# Sheet4.net
KiCad netlist of a schematic drawn in Altium Designer
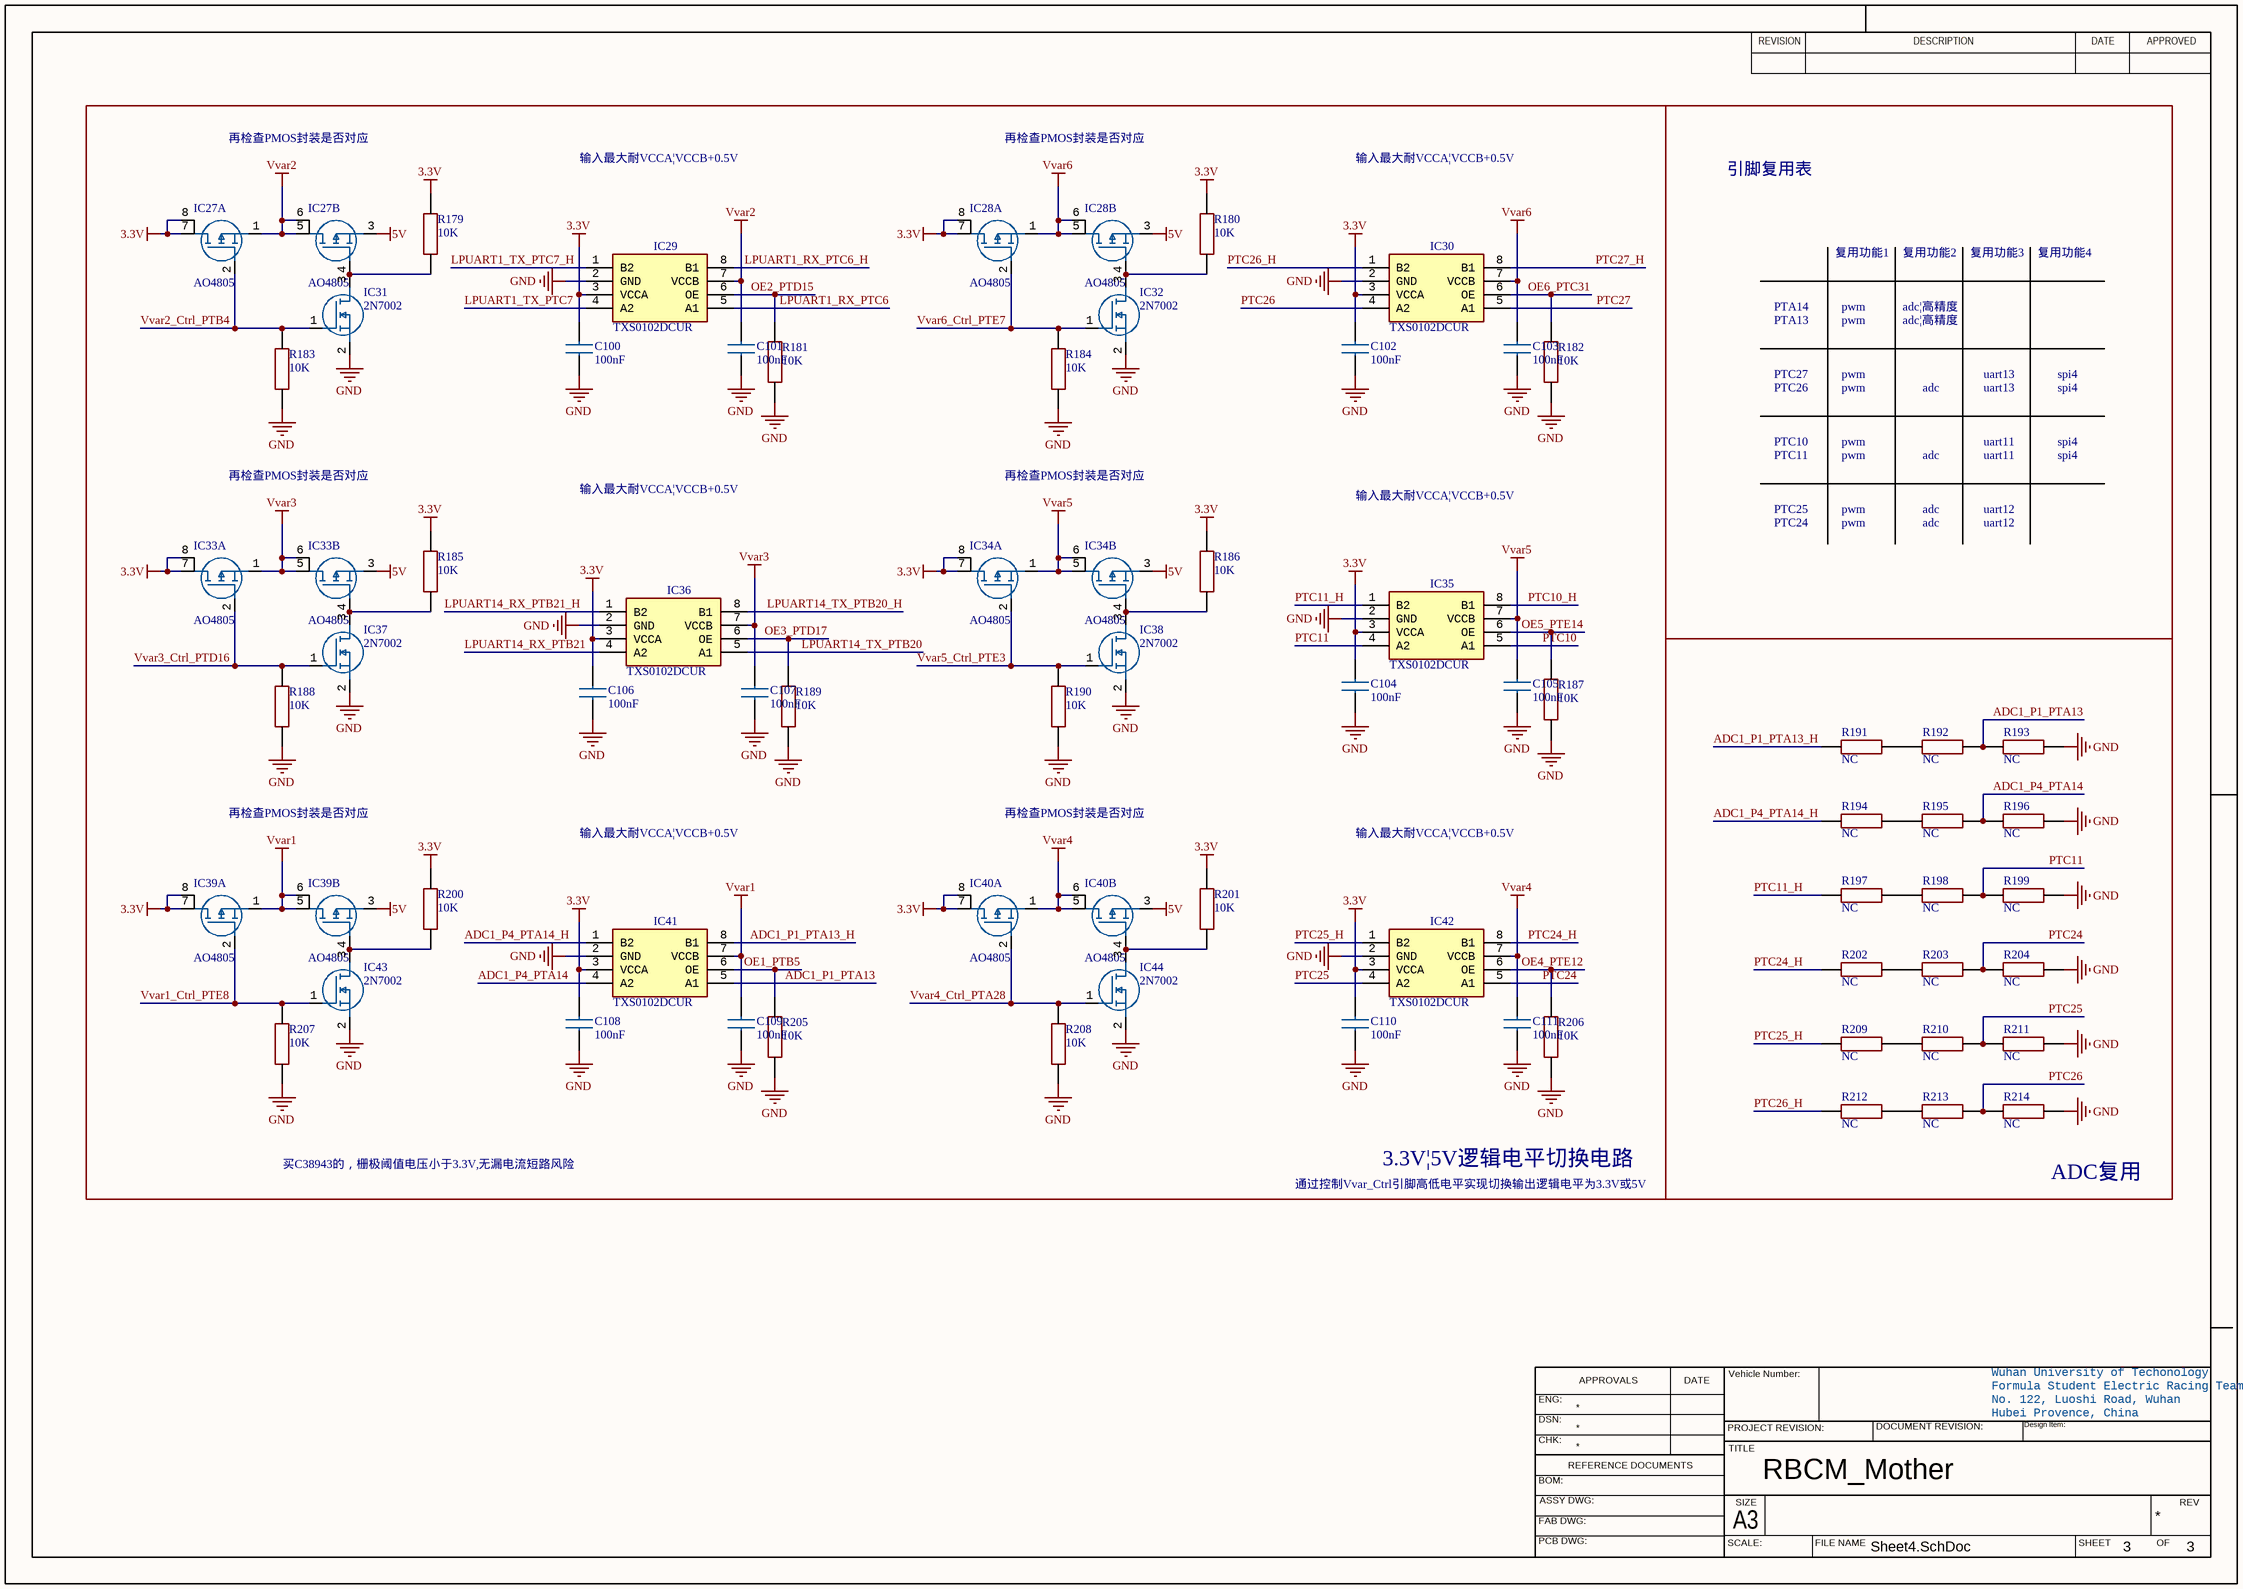
[diagram p0: Sheet4.SchDoc]

(export (version "E")
  (design (tool "Eeschema 10.0.6"))
  (components
    (comp (ref "C100")
      (value "100nF")
      (footprint "CAPC1608X90N")
      (description "Capacitor CC0603KRX7R9BB104")
      (fields
        (field (name "MANUFACTURER_PART_NUMBER") "CC0603KRX7R9BB104")
        (field (name "MOUSER PART NUMBER") "603-CC603KRX7R9BB104")
      )
      (libsource (lib "Resistor^Capacitor^Inductor") (part "C0603"))
    )
    (comp (ref "C101")
      (value "100nF")
      (footprint "CAPC1608X90N")
      (description "Capacitor CC0603KRX7R9BB104")
      (fields
        (field (name "MANUFACTURER_PART_NUMBER") "CC0603KRX7R9BB104")
        (field (name "MOUSER PART NUMBER") "603-CC603KRX7R9BB104")
      )
      (libsource (lib "Resistor^Capacitor^Inductor") (part "C0603"))
    )
    (comp (ref "C102")
      (value "100nF")
      (footprint "CAPC1608X90N")
      (description "Capacitor CC0603KRX7R9BB104")
      (fields
        (field (name "MANUFACTURER_PART_NUMBER") "CC0603KRX7R9BB104")
        (field (name "MOUSER PART NUMBER") "603-CC603KRX7R9BB104")
      )
      (libsource (lib "Resistor^Capacitor^Inductor") (part "C0603"))
    )
    (comp (ref "C103")
      (value "100nF")
      (footprint "CAPC1608X90N")
      (description "Capacitor CC0603KRX7R9BB104")
      (fields
        (field (name "MANUFACTURER_PART_NUMBER") "CC0603KRX7R9BB104")
        (field (name "MOUSER PART NUMBER") "603-CC603KRX7R9BB104")
      )
      (libsource (lib "Resistor^Capacitor^Inductor") (part "C0603"))
    )
    (comp (ref "C104")
      (value "100nF")
      (footprint "CAPC1608X90N")
      (description "Capacitor CC0603KRX7R9BB104")
      (fields
        (field (name "MANUFACTURER_PART_NUMBER") "CC0603KRX7R9BB104")
        (field (name "MOUSER PART NUMBER") "603-CC603KRX7R9BB104")
      )
      (libsource (lib "Resistor^Capacitor^Inductor") (part "C0603"))
    )
    (comp (ref "C105")
      (value "100nF")
      (footprint "CAPC1608X90N")
      (description "Capacitor CC0603KRX7R9BB104")
      (fields
        (field (name "MANUFACTURER_PART_NUMBER") "CC0603KRX7R9BB104")
        (field (name "MOUSER PART NUMBER") "603-CC603KRX7R9BB104")
      )
      (libsource (lib "Resistor^Capacitor^Inductor") (part "C0603"))
    )
    (comp (ref "C106")
      (value "100nF")
      (footprint "CAPC1608X90N")
      (description "Capacitor CC0603KRX7R9BB104")
      (fields
        (field (name "MANUFACTURER_PART_NUMBER") "CC0603KRX7R9BB104")
        (field (name "MOUSER PART NUMBER") "603-CC603KRX7R9BB104")
      )
      (libsource (lib "Resistor^Capacitor^Inductor") (part "C0603"))
    )
    (comp (ref "C107")
      (value "100nF")
      (footprint "CAPC1608X90N")
      (description "Capacitor CC0603KRX7R9BB104")
      (fields
        (field (name "MANUFACTURER_PART_NUMBER") "CC0603KRX7R9BB104")
        (field (name "MOUSER PART NUMBER") "603-CC603KRX7R9BB104")
      )
      (libsource (lib "Resistor^Capacitor^Inductor") (part "C0603"))
    )
    (comp (ref "C108")
      (value "100nF")
      (footprint "CAPC1608X90N")
      (description "Capacitor CC0603KRX7R9BB104")
      (fields
        (field (name "MANUFACTURER_PART_NUMBER") "CC0603KRX7R9BB104")
        (field (name "MOUSER PART NUMBER") "603-CC603KRX7R9BB104")
      )
      (libsource (lib "Resistor^Capacitor^Inductor") (part "C0603"))
    )
    (comp (ref "C109")
      (value "100nF")
      (footprint "CAPC1608X90N")
      (description "Capacitor CC0603KRX7R9BB104")
      (fields
        (field (name "MANUFACTURER_PART_NUMBER") "CC0603KRX7R9BB104")
        (field (name "MOUSER PART NUMBER") "603-CC603KRX7R9BB104")
      )
      (libsource (lib "Resistor^Capacitor^Inductor") (part "C0603"))
    )
    (comp (ref "C110")
      (value "100nF")
      (footprint "CAPC1608X90N")
      (description "Capacitor CC0603KRX7R9BB104")
      (fields
        (field (name "MANUFACTURER_PART_NUMBER") "CC0603KRX7R9BB104")
        (field (name "MOUSER PART NUMBER") "603-CC603KRX7R9BB104")
      )
      (libsource (lib "Resistor^Capacitor^Inductor") (part "C0603"))
    )
    (comp (ref "C111")
      (value "100nF")
      (footprint "CAPC1608X90N")
      (description "Capacitor CC0603KRX7R9BB104")
      (fields
        (field (name "MANUFACTURER_PART_NUMBER") "CC0603KRX7R9BB104")
        (field (name "MOUSER PART NUMBER") "603-CC603KRX7R9BB104")
      )
      (libsource (lib "Resistor^Capacitor^Inductor") (part "C0603"))
    )
    (comp (ref "IC27")
      (value "AO4805")
      (footprint "Triode^MOS^Transistor:SOIC127P600X175-8N_AO4805")
      (description "Integrated Circuit")
      (libsource (lib "") (part "AO4805_1"))
    )
    (comp (ref "IC28")
      (value "AO4805")
      (footprint "Triode^MOS^Transistor:SOIC127P600X175-8N_AO4805")
      (description "Integrated Circuit")
      (libsource (lib "") (part "AO4805_1"))
    )
    (comp (ref "IC29")
      (value "TXS0102DCUR")
      (footprint "SOP50P310X90-8N")
      (description "Integrated Circuit")
      (fields (field (name "MOUSER PART NUMBER") "595-TXS0102DCUR"))
      (libsource (lib "Switch^Relay") (part "TXS0102DCUR"))
    )
    (comp (ref "IC30")
      (value "TXS0102DCUR")
      (footprint "SOP50P310X90-8N")
      (description "Integrated Circuit")
      (fields (field (name "MOUSER PART NUMBER") "595-TXS0102DCUR"))
      (libsource (lib "Switch^Relay") (part "TXS0102DCUR"))
    )
    (comp (ref "IC31")
      (value "2N7002")
      (footprint "SOT95P230X110-3N")
      (description "Integrated Circuit")
      (fields (field (name "MANUFACTURER_PART_NUMBER") "2N7002P,235"))
      (libsource (lib "Triode^MOS^Transistor") (part "2N7002"))
    )
    (comp (ref "IC32")
      (value "2N7002")
      (footprint "SOT95P230X110-3N")
      (description "Integrated Circuit")
      (fields (field (name "MANUFACTURER_PART_NUMBER") "2N7002P,235"))
      (libsource (lib "Triode^MOS^Transistor") (part "2N7002"))
    )
    (comp (ref "IC33")
      (value "AO4805")
      (footprint "Triode^MOS^Transistor:SOIC127P600X175-8N_AO4805")
      (description "Integrated Circuit")
      (libsource (lib "") (part "AO4805_1"))
    )
    (comp (ref "IC34")
      (value "AO4805")
      (footprint "Triode^MOS^Transistor:SOIC127P600X175-8N_AO4805")
      (description "Integrated Circuit")
      (libsource (lib "Triode^MOS^Transistor") (part "AO4805"))
    )
    (comp (ref "IC35")
      (value "TXS0102DCUR")
      (footprint "SOP50P310X90-8N")
      (description "Integrated Circuit")
      (fields (field (name "MOUSER PART NUMBER") "595-TXS0102DCUR"))
      (libsource (lib "Switch^Relay") (part "TXS0102DCUR"))
    )
    (comp (ref "IC36")
      (value "TXS0102DCUR")
      (footprint "SOP50P310X90-8N")
      (description "Integrated Circuit")
      (fields (field (name "MOUSER PART NUMBER") "595-TXS0102DCUR"))
      (libsource (lib "Switch^Relay") (part "TXS0102DCUR"))
    )
    (comp (ref "IC37")
      (value "2N7002")
      (footprint "SOT95P230X110-3N")
      (description "Integrated Circuit")
      (fields (field (name "MANUFACTURER_PART_NUMBER") "2N7002P,235"))
      (libsource (lib "Triode^MOS^Transistor") (part "2N7002"))
    )
    (comp (ref "IC38")
      (value "2N7002")
      (footprint "SOT95P230X110-3N")
      (description "Integrated Circuit")
      (fields (field (name "MANUFACTURER_PART_NUMBER") "2N7002P,235"))
      (libsource (lib "Triode^MOS^Transistor") (part "2N7002"))
    )
    (comp (ref "IC39")
      (value "AO4805")
      (footprint "Triode^MOS^Transistor:SOIC127P600X175-8N_AO4805")
      (description "Integrated Circuit")
      (libsource (lib "Triode^MOS^Transistor") (part "AO4805"))
    )
    (comp (ref "IC40")
      (value "AO4805")
      (footprint "Triode^MOS^Transistor:SOIC127P600X175-8N_AO4805")
      (description "Integrated Circuit")
      (libsource (lib "Triode^MOS^Transistor") (part "AO4805"))
    )
    (comp (ref "IC41")
      (value "TXS0102DCUR")
      (footprint "SOP50P310X90-8N")
      (description "Integrated Circuit")
      (fields (field (name "MOUSER PART NUMBER") "595-TXS0102DCUR"))
      (libsource (lib "Switch^Relay") (part "TXS0102DCUR"))
    )
    (comp (ref "IC42")
      (value "TXS0102DCUR")
      (footprint "SOP50P310X90-8N")
      (description "Integrated Circuit")
      (fields (field (name "MOUSER PART NUMBER") "595-TXS0102DCUR"))
      (libsource (lib "Switch^Relay") (part "TXS0102DCUR"))
    )
    (comp (ref "IC43")
      (value "2N7002")
      (footprint "SOT95P230X110-3N")
      (description "Integrated Circuit")
      (fields (field (name "MANUFACTURER_PART_NUMBER") "2N7002P,235"))
      (libsource (lib "Triode^MOS^Transistor") (part "2N7002"))
    )
    (comp (ref "IC44")
      (value "2N7002")
      (footprint "SOT95P230X110-3N")
      (description "Integrated Circuit")
      (fields (field (name "MANUFACTURER_PART_NUMBER") "2N7002P,235"))
      (libsource (lib "Triode^MOS^Transistor") (part "2N7002"))
    )
    (comp (ref "R179")
      (value "10K")
      (footprint "RESC1608X55N")
      (description "Resistor")
      (fields (field (name "MANUFACTURER_PART_NUMBER") "0603WAF1002T5E"))
      (libsource (lib "") (part "R0603_2"))
    )
    (comp (ref "R180")
      (value "10K")
      (footprint "RESC1608X55N")
      (description "Resistor")
      (fields (field (name "MANUFACTURER_PART_NUMBER") "0603WAF1002T5E"))
      (libsource (lib "") (part "R0603_2"))
    )
    (comp (ref "R181")
      (value "10K")
      (footprint "RESC1608X55N")
      (description "Resistor 0603WAF1002T5E")
      (fields (field (name "MANUFACTURER_PART_NUMBER") "0603WAF1002T5E"))
      (libsource (lib "Resistor^Capacitor^Inductor") (part "R0603"))
    )
    (comp (ref "R182")
      (value "10K")
      (footprint "RESC1608X55N")
      (description "Resistor 0603WAF1002T5E")
      (fields (field (name "MANUFACTURER_PART_NUMBER") "0603WAF1002T5E"))
      (libsource (lib "Resistor^Capacitor^Inductor") (part "R0603"))
    )
    (comp (ref "R183")
      (value "10K")
      (footprint "RESC1608X55N")
      (description "Resistor")
      (fields (field (name "MANUFACTURER_PART_NUMBER") "0603WAF1002T5E"))
      (libsource (lib "") (part "R0603_2"))
    )
    (comp (ref "R184")
      (value "10K")
      (footprint "RESC1608X55N")
      (description "Resistor")
      (fields (field (name "MANUFACTURER_PART_NUMBER") "0603WAF1002T5E"))
      (libsource (lib "") (part "R0603_2"))
    )
    (comp (ref "R185")
      (value "10K")
      (footprint "RESC1608X55N")
      (description "Resistor")
      (fields (field (name "MANUFACTURER_PART_NUMBER") "0603WAF1002T5E"))
      (libsource (lib "") (part "R0603_2"))
    )
    (comp (ref "R186")
      (value "10K")
      (footprint "RESC1608X55N")
      (description "Resistor")
      (fields (field (name "MANUFACTURER_PART_NUMBER") "0603WAF1002T5E"))
      (libsource (lib "") (part "R0603_2"))
    )
    (comp (ref "R187")
      (value "10K")
      (footprint "RESC1608X55N")
      (description "Resistor 0603WAF1002T5E")
      (fields (field (name "MANUFACTURER_PART_NUMBER") "0603WAF1002T5E"))
      (libsource (lib "Resistor^Capacitor^Inductor") (part "R0603"))
    )
    (comp (ref "R188")
      (value "10K")
      (footprint "RESC1608X55N")
      (description "Resistor")
      (fields (field (name "MANUFACTURER_PART_NUMBER") "0603WAF1002T5E"))
      (libsource (lib "") (part "R0603_2"))
    )
    (comp (ref "R189")
      (value "10K")
      (footprint "RESC1608X55N")
      (description "Resistor 0603WAF1002T5E")
      (fields (field (name "MANUFACTURER_PART_NUMBER") "0603WAF1002T5E"))
      (libsource (lib "Resistor^Capacitor^Inductor") (part "R0603"))
    )
    (comp (ref "R190")
      (value "10K")
      (footprint "RESC1608X55N")
      (description "Resistor")
      (fields (field (name "MANUFACTURER_PART_NUMBER") "0603WAF1002T5E"))
      (libsource (lib "") (part "R0603_2"))
    )
    (comp (ref "R191")
      (value "NC")
      (footprint "RESC1608X55N")
      (description "Resistor")
      (fields (field (name "MANUFACTURER_PART_NUMBER") "0603WAF1002T5E"))
      (libsource (lib "") (part "R0603_1"))
    )
    (comp (ref "R192")
      (value "NC")
      (footprint "RESC1608X55N")
      (description "Resistor")
      (fields (field (name "MANUFACTURER_PART_NUMBER") "0603WAF1002T5E"))
      (libsource (lib "") (part "R0603_1"))
    )
    (comp (ref "R193")
      (value "NC")
      (footprint "RESC1608X55N")
      (description "Resistor")
      (fields (field (name "MANUFACTURER_PART_NUMBER") "0603WAF1002T5E"))
      (libsource (lib "") (part "R0603_1"))
    )
    (comp (ref "R194")
      (value "NC")
      (footprint "RESC1608X55N")
      (description "Resistor")
      (fields (field (name "MANUFACTURER_PART_NUMBER") "0603WAF1002T5E"))
      (libsource (lib "") (part "R0603_1"))
    )
    (comp (ref "R195")
      (value "NC")
      (footprint "RESC1608X55N")
      (description "Resistor")
      (fields (field (name "MANUFACTURER_PART_NUMBER") "0603WAF1002T5E"))
      (libsource (lib "") (part "R0603_1"))
    )
    (comp (ref "R196")
      (value "NC")
      (footprint "RESC1608X55N")
      (description "Resistor")
      (fields (field (name "MANUFACTURER_PART_NUMBER") "0603WAF1002T5E"))
      (libsource (lib "") (part "R0603_1"))
    )
    (comp (ref "R197")
      (value "NC")
      (footprint "RESC1608X55N")
      (description "Resistor")
      (fields (field (name "MANUFACTURER_PART_NUMBER") "0603WAF1002T5E"))
      (libsource (lib "") (part "R0603_1"))
    )
    (comp (ref "R198")
      (value "NC")
      (footprint "RESC1608X55N")
      (description "Resistor")
      (fields (field (name "MANUFACTURER_PART_NUMBER") "0603WAF1002T5E"))
      (libsource (lib "") (part "R0603_1"))
    )
    (comp (ref "R199")
      (value "NC")
      (footprint "RESC1608X55N")
      (description "Resistor")
      (fields (field (name "MANUFACTURER_PART_NUMBER") "0603WAF1002T5E"))
      (libsource (lib "") (part "R0603_1"))
    )
    (comp (ref "R200")
      (value "10K")
      (footprint "RESC1608X55N")
      (description "Resistor")
      (fields (field (name "MANUFACTURER_PART_NUMBER") "0603WAF1002T5E"))
      (libsource (lib "") (part "R0603_2"))
    )
    (comp (ref "R201")
      (value "10K")
      (footprint "RESC1608X55N")
      (description "Resistor")
      (fields (field (name "MANUFACTURER_PART_NUMBER") "0603WAF1002T5E"))
      (libsource (lib "") (part "R0603_2"))
    )
    (comp (ref "R202")
      (value "NC")
      (footprint "RESC1608X55N")
      (description "Resistor")
      (fields (field (name "MANUFACTURER_PART_NUMBER") "0603WAF1002T5E"))
      (libsource (lib "") (part "R0603_1"))
    )
    (comp (ref "R203")
      (value "NC")
      (footprint "RESC1608X55N")
      (description "Resistor")
      (fields (field (name "MANUFACTURER_PART_NUMBER") "0603WAF1002T5E"))
      (libsource (lib "") (part "R0603_1"))
    )
    (comp (ref "R204")
      (value "NC")
      (footprint "RESC1608X55N")
      (description "Resistor")
      (fields (field (name "MANUFACTURER_PART_NUMBER") "0603WAF1002T5E"))
      (libsource (lib "") (part "R0603_1"))
    )
    (comp (ref "R205")
      (value "10K")
      (footprint "RESC1608X55N")
      (description "Resistor 0603WAF1002T5E")
      (fields (field (name "MANUFACTURER_PART_NUMBER") "0603WAF1002T5E"))
      (libsource (lib "Resistor^Capacitor^Inductor") (part "R0603"))
    )
    (comp (ref "R206")
      (value "10K")
      (footprint "RESC1608X55N")
      (description "Resistor 0603WAF1002T5E")
      (fields (field (name "MANUFACTURER_PART_NUMBER") "0603WAF1002T5E"))
      (libsource (lib "Resistor^Capacitor^Inductor") (part "R0603"))
    )
    (comp (ref "R207")
      (value "10K")
      (footprint "RESC1608X55N")
      (description "Resistor")
      (fields (field (name "MANUFACTURER_PART_NUMBER") "0603WAF1002T5E"))
      (libsource (lib "") (part "R0603_2"))
    )
    (comp (ref "R208")
      (value "10K")
      (footprint "RESC1608X55N")
      (description "Resistor")
      (fields (field (name "MANUFACTURER_PART_NUMBER") "0603WAF1002T5E"))
      (libsource (lib "") (part "R0603_2"))
    )
    (comp (ref "R209")
      (value "NC")
      (footprint "RESC1608X55N")
      (description "Resistor")
      (fields (field (name "MANUFACTURER_PART_NUMBER") "0603WAF1002T5E"))
      (libsource (lib "") (part "R0603_1"))
    )
    (comp (ref "R210")
      (value "NC")
      (footprint "RESC1608X55N")
      (description "Resistor")
      (fields (field (name "MANUFACTURER_PART_NUMBER") "0603WAF1002T5E"))
      (libsource (lib "") (part "R0603_1"))
    )
    (comp (ref "R211")
      (value "NC")
      (footprint "RESC1608X55N")
      (description "Resistor")
      (fields (field (name "MANUFACTURER_PART_NUMBER") "0603WAF1002T5E"))
      (libsource (lib "") (part "R0603_1"))
    )
    (comp (ref "R212")
      (value "NC")
      (footprint "RESC1608X55N")
      (description "Resistor")
      (fields (field (name "MANUFACTURER_PART_NUMBER") "0603WAF1002T5E"))
      (libsource (lib "") (part "R0603_1"))
    )
    (comp (ref "R213")
      (value "NC")
      (footprint "RESC1608X55N")
      (description "Resistor")
      (fields (field (name "MANUFACTURER_PART_NUMBER") "0603WAF1002T5E"))
      (libsource (lib "") (part "R0603_1"))
    )
    (comp (ref "R214")
      (value "NC")
      (footprint "RESC1608X55N")
      (description "Resistor")
      (fields (field (name "MANUFACTURER_PART_NUMBER") "0603WAF1002T5E"))
      (libsource (lib "") (part "R0603_1"))
    )
  )
  (nets
    (net (code "2") (name "/ADC1_P1_PTA13") (class "Default")
      (node (ref "IC41") (pin "5") (pinfunction "A1_5") (pintype "passive"))
      (node (ref "R192") (pin "2") (pinfunction "2_2") (pintype "passive"))
      (node (ref "R193") (pin "1") (pinfunction "1_1") (pintype "passive"))
    )
    (net (code "3") (name "/ADC1_P1_PTA13_H") (class "Default")
      (node (ref "IC41") (pin "8") (pinfunction "B1_8") (pintype "passive"))
      (node (ref "R191") (pin "1") (pinfunction "1_1") (pintype "passive"))
    )
    (net (code "4") (name "/ADC1_P4_PTA14") (class "Default")
      (node (ref "IC41") (pin "4") (pinfunction "A2_4") (pintype "passive"))
      (node (ref "R195") (pin "2") (pinfunction "2_2") (pintype "passive"))
      (node (ref "R196") (pin "1") (pinfunction "1_1") (pintype "passive"))
    )
    (net (code "5") (name "/ADC1_P4_PTA14_H") (class "Default")
      (node (ref "IC41") (pin "1") (pinfunction "B2_1") (pintype "passive"))
      (node (ref "R194") (pin "1") (pinfunction "1_1") (pintype "passive"))
    )
    (net (code "6") (name "/LPUART1_RX_PTC6") (class "Default")
      (node (ref "IC29") (pin "5") (pinfunction "A1_5") (pintype "passive"))
    )
    (net (code "7") (name "/LPUART1_RX_PTC6_H") (class "Default")
      (node (ref "IC29") (pin "8") (pinfunction "B1_8") (pintype "passive"))
    )
    (net (code "8") (name "/LPUART1_TX_PTC7") (class "Default")
      (node (ref "IC29") (pin "4") (pinfunction "A2_4") (pintype "passive"))
    )
    (net (code "9") (name "/LPUART1_TX_PTC7_H") (class "Default")
      (node (ref "IC29") (pin "1") (pinfunction "B2_1") (pintype "passive"))
    )
    (net (code "10") (name "/LPUART14_RX_PTB21") (class "Default")
      (node (ref "IC36") (pin "4") (pinfunction "A2_4") (pintype "passive"))
    )
    (net (code "11") (name "/LPUART14_RX_PTB21_H") (class "Default")
      (node (ref "IC36") (pin "1") (pinfunction "B2_1") (pintype "passive"))
    )
    (net (code "12") (name "/LPUART14_TX_PTB20") (class "Default")
      (node (ref "IC36") (pin "5") (pinfunction "A1_5") (pintype "passive"))
    )
    (net (code "13") (name "/LPUART14_TX_PTB20_H") (class "Default")
      (node (ref "IC36") (pin "8") (pinfunction "B1_8") (pintype "passive"))
    )
    (net (code "14") (name "/OE1_PTB5") (class "Default")
      (node (ref "IC41") (pin "6") (pinfunction "OE_6") (pintype "passive"))
      (node (ref "R205") (pin "1") (pinfunction "1_1") (pintype "passive"))
    )
    (net (code "15") (name "/OE2_PTD15") (class "Default")
      (node (ref "IC29") (pin "6") (pinfunction "OE_6") (pintype "passive"))
      (node (ref "R181") (pin "1") (pinfunction "1_1") (pintype "passive"))
    )
    (net (code "16") (name "/OE3_PTD17") (class "Default")
      (node (ref "IC36") (pin "6") (pinfunction "OE_6") (pintype "passive"))
      (node (ref "R189") (pin "1") (pinfunction "1_1") (pintype "passive"))
    )
    (net (code "17") (name "/OE4_PTE12") (class "Default")
      (node (ref "IC42") (pin "6") (pinfunction "OE_6") (pintype "passive"))
      (node (ref "R206") (pin "1") (pinfunction "1_1") (pintype "passive"))
    )
    (net (code "18") (name "/OE5_PTE14") (class "Default")
      (node (ref "IC35") (pin "6") (pinfunction "OE_6") (pintype "passive"))
      (node (ref "R187") (pin "1") (pinfunction "1_1") (pintype "passive"))
    )
    (net (code "19") (name "/OE6_PTC31") (class "Default")
      (node (ref "IC30") (pin "6") (pinfunction "OE_6") (pintype "passive"))
      (node (ref "R182") (pin "1") (pinfunction "1_1") (pintype "passive"))
    )
    (net (code "20") (name "/PTC10") (class "Default")
      (node (ref "IC35") (pin "5") (pinfunction "A1_5") (pintype "passive"))
    )
    (net (code "21") (name "/PTC10_H") (class "Default")
      (node (ref "IC35") (pin "8") (pinfunction "B1_8") (pintype "passive"))
    )
    (net (code "22") (name "/PTC11") (class "Default")
      (node (ref "IC35") (pin "4") (pinfunction "A2_4") (pintype "passive"))
      (node (ref "R198") (pin "2") (pinfunction "2_2") (pintype "passive"))
      (node (ref "R199") (pin "1") (pinfunction "1_1") (pintype "passive"))
    )
    (net (code "23") (name "/PTC11_H") (class "Default")
      (node (ref "IC35") (pin "1") (pinfunction "B2_1") (pintype "passive"))
      (node (ref "R197") (pin "1") (pinfunction "1_1") (pintype "passive"))
    )
    (net (code "24") (name "/PTC24") (class "Default")
      (node (ref "IC42") (pin "5") (pinfunction "A1_5") (pintype "passive"))
      (node (ref "R203") (pin "2") (pinfunction "2_2") (pintype "passive"))
      (node (ref "R204") (pin "1") (pinfunction "1_1") (pintype "passive"))
    )
    (net (code "25") (name "/PTC24_H") (class "Default")
      (node (ref "IC42") (pin "8") (pinfunction "B1_8") (pintype "passive"))
      (node (ref "R202") (pin "1") (pinfunction "1_1") (pintype "passive"))
    )
    (net (code "26") (name "/PTC25") (class "Default")
      (node (ref "IC42") (pin "4") (pinfunction "A2_4") (pintype "passive"))
      (node (ref "R210") (pin "2") (pinfunction "2_2") (pintype "passive"))
      (node (ref "R211") (pin "1") (pinfunction "1_1") (pintype "passive"))
    )
    (net (code "27") (name "/PTC25_H") (class "Default")
      (node (ref "IC42") (pin "1") (pinfunction "B2_1") (pintype "passive"))
      (node (ref "R209") (pin "1") (pinfunction "1_1") (pintype "passive"))
    )
    (net (code "28") (name "/PTC26") (class "Default")
      (node (ref "IC30") (pin "4") (pinfunction "A2_4") (pintype "passive"))
      (node (ref "R213") (pin "2") (pinfunction "2_2") (pintype "passive"))
      (node (ref "R214") (pin "1") (pinfunction "1_1") (pintype "passive"))
    )
    (net (code "29") (name "/PTC26_H") (class "Default")
      (node (ref "IC30") (pin "1") (pinfunction "B2_1") (pintype "passive"))
      (node (ref "R212") (pin "1") (pinfunction "1_1") (pintype "passive"))
    )
    (net (code "30") (name "/PTC27") (class "Default")
      (node (ref "IC30") (pin "5") (pinfunction "A1_5") (pintype "passive"))
    )
    (net (code "31") (name "/PTC27_H") (class "Default")
      (node (ref "IC30") (pin "8") (pinfunction "B1_8") (pintype "passive"))
    )
    (net (code "32") (name "/Vvar1_Ctrl_PTE8") (class "Default")
      (node (ref "IC39") (pin "2") (pinfunction "G2_2") (pintype "passive"))
      (node (ref "IC43") (pin "1") (pinfunction "G_1") (pintype "passive"))
      (node (ref "R207") (pin "1") (pinfunction "1_1") (pintype "passive"))
    )
    (net (code "33") (name "/Vvar2_Ctrl_PTB4") (class "Default")
      (node (ref "IC27") (pin "2") (pinfunction "G2_2") (pintype "passive"))
      (node (ref "IC31") (pin "1") (pinfunction "G_1") (pintype "passive"))
      (node (ref "R183") (pin "1") (pinfunction "1_1") (pintype "passive"))
    )
    (net (code "34") (name "/Vvar3_Ctrl_PTD16") (class "Default")
      (node (ref "IC33") (pin "2") (pinfunction "G2_2") (pintype "passive"))
      (node (ref "IC37") (pin "1") (pinfunction "G_1") (pintype "passive"))
      (node (ref "R188") (pin "1") (pinfunction "1_1") (pintype "passive"))
    )
    (net (code "35") (name "/Vvar4_Ctrl_PTA28") (class "Default")
      (node (ref "IC40") (pin "2") (pinfunction "G2_2") (pintype "passive"))
      (node (ref "IC44") (pin "1") (pinfunction "G_1") (pintype "passive"))
      (node (ref "R208") (pin "1") (pinfunction "1_1") (pintype "passive"))
    )
    (net (code "36") (name "/Vvar5_Ctrl_PTE3") (class "Default")
      (node (ref "IC34") (pin "2") (pinfunction "G2_2") (pintype "passive"))
      (node (ref "IC38") (pin "1") (pinfunction "G_1") (pintype "passive"))
      (node (ref "R190") (pin "1") (pinfunction "1_1") (pintype "passive"))
    )
    (net (code "37") (name "/Vvar6_Ctrl_PTE7") (class "Default")
      (node (ref "IC28") (pin "2") (pinfunction "G2_2") (pintype "passive"))
      (node (ref "IC32") (pin "1") (pinfunction "G_1") (pintype "passive"))
      (node (ref "R184") (pin "1") (pinfunction "1_1") (pintype "passive"))
    )
    (net (code "38") (name "3.3V") (class "Default")
      (node (ref "C100") (pin "1") (pinfunction "1_1") (pintype "passive"))
      (node (ref "C102") (pin "1") (pinfunction "1_1") (pintype "passive"))
      (node (ref "C104") (pin "1") (pinfunction "1_1") (pintype "passive"))
      (node (ref "C106") (pin "1") (pinfunction "1_1") (pintype "passive"))
      (node (ref "C108") (pin "1") (pinfunction "1_1") (pintype "passive"))
      (node (ref "C110") (pin "1") (pinfunction "1_1") (pintype "passive"))
      (node (ref "IC27") (pin "7") (pinfunction "D2_7") (pintype "passive"))
      (node (ref "IC27") (pin "8") (pinfunction "D2_8") (pintype "passive"))
      (node (ref "IC28") (pin "7") (pinfunction "D2_7") (pintype "passive"))
      (node (ref "IC28") (pin "8") (pinfunction "D2_8") (pintype "passive"))
      (node (ref "IC29") (pin "3") (pinfunction "VCCA_3") (pintype "passive"))
      (node (ref "IC30") (pin "3") (pinfunction "VCCA_3") (pintype "passive"))
      (node (ref "IC33") (pin "7") (pinfunction "D2_7") (pintype "passive"))
      (node (ref "IC33") (pin "8") (pinfunction "D2_8") (pintype "passive"))
      (node (ref "IC34") (pin "7") (pinfunction "D2_7") (pintype "passive"))
      (node (ref "IC34") (pin "8") (pinfunction "D2_8") (pintype "passive"))
      (node (ref "IC35") (pin "3") (pinfunction "VCCA_3") (pintype "passive"))
      (node (ref "IC36") (pin "3") (pinfunction "VCCA_3") (pintype "passive"))
      (node (ref "IC39") (pin "7") (pinfunction "D2_7") (pintype "passive"))
      (node (ref "IC39") (pin "8") (pinfunction "D2_8") (pintype "passive"))
      (node (ref "IC40") (pin "7") (pinfunction "D2_7") (pintype "passive"))
      (node (ref "IC40") (pin "8") (pinfunction "D2_8") (pintype "passive"))
      (node (ref "IC41") (pin "3") (pinfunction "VCCA_3") (pintype "passive"))
      (node (ref "IC42") (pin "3") (pinfunction "VCCA_3") (pintype "passive"))
      (node (ref "R179") (pin "1") (pinfunction "1_1") (pintype "passive"))
      (node (ref "R180") (pin "1") (pinfunction "1_1") (pintype "passive"))
      (node (ref "R185") (pin "1") (pinfunction "1_1") (pintype "passive"))
      (node (ref "R186") (pin "1") (pinfunction "1_1") (pintype "passive"))
      (node (ref "R200") (pin "1") (pinfunction "1_1") (pintype "passive"))
      (node (ref "R201") (pin "1") (pinfunction "1_1") (pintype "passive"))
    )
    (net (code "39") (name "5V") (class "Default")
      (node (ref "IC27") (pin "3") (pinfunction "S1_3") (pintype "passive"))
      (node (ref "IC28") (pin "3") (pinfunction "S1_3") (pintype "passive"))
      (node (ref "IC33") (pin "3") (pinfunction "S1_3") (pintype "passive"))
      (node (ref "IC34") (pin "3") (pinfunction "S1_3") (pintype "passive"))
      (node (ref "IC39") (pin "3") (pinfunction "S1_3") (pintype "passive"))
      (node (ref "IC40") (pin "3") (pinfunction "S1_3") (pintype "passive"))
    )
    (net (code "40") (name "GND") (class "Default")
      (node (ref "C100") (pin "2") (pinfunction "2_2") (pintype "passive"))
      (node (ref "C101") (pin "2") (pinfunction "2_2") (pintype "passive"))
      (node (ref "C102") (pin "2") (pinfunction "2_2") (pintype "passive"))
      (node (ref "C103") (pin "2") (pinfunction "2_2") (pintype "passive"))
      (node (ref "C104") (pin "2") (pinfunction "2_2") (pintype "passive"))
      (node (ref "C105") (pin "2") (pinfunction "2_2") (pintype "passive"))
      (node (ref "C106") (pin "2") (pinfunction "2_2") (pintype "passive"))
      (node (ref "C107") (pin "2") (pinfunction "2_2") (pintype "passive"))
      (node (ref "C108") (pin "2") (pinfunction "2_2") (pintype "passive"))
      (node (ref "C109") (pin "2") (pinfunction "2_2") (pintype "passive"))
      (node (ref "C110") (pin "2") (pinfunction "2_2") (pintype "passive"))
      (node (ref "C111") (pin "2") (pinfunction "2_2") (pintype "passive"))
      (node (ref "IC29") (pin "2") (pinfunction "GND_2") (pintype "passive"))
      (node (ref "IC30") (pin "2") (pinfunction "GND_2") (pintype "passive"))
      (node (ref "IC31") (pin "2") (pinfunction "S_2") (pintype "passive"))
      (node (ref "IC32") (pin "2") (pinfunction "S_2") (pintype "passive"))
      (node (ref "IC35") (pin "2") (pinfunction "GND_2") (pintype "passive"))
      (node (ref "IC36") (pin "2") (pinfunction "GND_2") (pintype "passive"))
      (node (ref "IC37") (pin "2") (pinfunction "S_2") (pintype "passive"))
      (node (ref "IC38") (pin "2") (pinfunction "S_2") (pintype "passive"))
      (node (ref "IC41") (pin "2") (pinfunction "GND_2") (pintype "passive"))
      (node (ref "IC42") (pin "2") (pinfunction "GND_2") (pintype "passive"))
      (node (ref "IC43") (pin "2") (pinfunction "S_2") (pintype "passive"))
      (node (ref "IC44") (pin "2") (pinfunction "S_2") (pintype "passive"))
      (node (ref "R181") (pin "2") (pinfunction "2_2") (pintype "passive"))
      (node (ref "R182") (pin "2") (pinfunction "2_2") (pintype "passive"))
      (node (ref "R183") (pin "2") (pinfunction "2_2") (pintype "passive"))
      (node (ref "R184") (pin "2") (pinfunction "2_2") (pintype "passive"))
      (node (ref "R187") (pin "2") (pinfunction "2_2") (pintype "passive"))
      (node (ref "R188") (pin "2") (pinfunction "2_2") (pintype "passive"))
      (node (ref "R189") (pin "2") (pinfunction "2_2") (pintype "passive"))
      (node (ref "R190") (pin "2") (pinfunction "2_2") (pintype "passive"))
      (node (ref "R193") (pin "2") (pinfunction "2_2") (pintype "passive"))
      (node (ref "R196") (pin "2") (pinfunction "2_2") (pintype "passive"))
      (node (ref "R199") (pin "2") (pinfunction "2_2") (pintype "passive"))
      (node (ref "R204") (pin "2") (pinfunction "2_2") (pintype "passive"))
      (node (ref "R205") (pin "2") (pinfunction "2_2") (pintype "passive"))
      (node (ref "R206") (pin "2") (pinfunction "2_2") (pintype "passive"))
      (node (ref "R207") (pin "2") (pinfunction "2_2") (pintype "passive"))
      (node (ref "R208") (pin "2") (pinfunction "2_2") (pintype "passive"))
      (node (ref "R211") (pin "2") (pinfunction "2_2") (pintype "passive"))
      (node (ref "R214") (pin "2") (pinfunction "2_2") (pintype "passive"))
    )
    (net (code "41") (name "Net-(IC27B-G1)") (class "Default")
      (node (ref "IC27") (pin "4") (pinfunction "G1_4") (pintype "passive"))
      (node (ref "IC31") (pin "3") (pinfunction "D_3") (pintype "passive"))
      (node (ref "R179") (pin "2") (pinfunction "2_2") (pintype "passive"))
    )
    (net (code "42") (name "Net-(IC28B-G1)") (class "Default")
      (node (ref "IC28") (pin "4") (pinfunction "G1_4") (pintype "passive"))
      (node (ref "IC32") (pin "3") (pinfunction "D_3") (pintype "passive"))
      (node (ref "R180") (pin "2") (pinfunction "2_2") (pintype "passive"))
    )
    (net (code "43") (name "Net-(IC33B-G1)") (class "Default")
      (node (ref "IC33") (pin "4") (pinfunction "G1_4") (pintype "passive"))
      (node (ref "IC37") (pin "3") (pinfunction "D_3") (pintype "passive"))
      (node (ref "R185") (pin "2") (pinfunction "2_2") (pintype "passive"))
    )
    (net (code "44") (name "Net-(IC34B-G1)") (class "Default")
      (node (ref "IC34") (pin "4") (pinfunction "G1_4") (pintype "passive"))
      (node (ref "IC38") (pin "3") (pinfunction "D_3") (pintype "passive"))
      (node (ref "R186") (pin "2") (pinfunction "2_2") (pintype "passive"))
    )
    (net (code "45") (name "Net-(IC39B-G1)") (class "Default")
      (node (ref "IC39") (pin "4") (pinfunction "G1_4") (pintype "passive"))
      (node (ref "IC43") (pin "3") (pinfunction "D_3") (pintype "passive"))
      (node (ref "R200") (pin "2") (pinfunction "2_2") (pintype "passive"))
    )
    (net (code "46") (name "Net-(IC40B-G1)") (class "Default")
      (node (ref "IC40") (pin "4") (pinfunction "G1_4") (pintype "passive"))
      (node (ref "IC44") (pin "3") (pinfunction "D_3") (pintype "passive"))
      (node (ref "R201") (pin "2") (pinfunction "2_2") (pintype "passive"))
    )
    (net (code "47") (name "Net-(R191-Pad2)") (class "Default")
      (node (ref "R191") (pin "2") (pinfunction "2_2") (pintype "passive"))
      (node (ref "R192") (pin "1") (pinfunction "1_1") (pintype "passive"))
    )
    (net (code "48") (name "Net-(R194-Pad2)") (class "Default")
      (node (ref "R194") (pin "2") (pinfunction "2_2") (pintype "passive"))
      (node (ref "R195") (pin "1") (pinfunction "1_1") (pintype "passive"))
    )
    (net (code "49") (name "Net-(R197-Pad2)") (class "Default")
      (node (ref "R197") (pin "2") (pinfunction "2_2") (pintype "passive"))
      (node (ref "R198") (pin "1") (pinfunction "1_1") (pintype "passive"))
    )
    (net (code "50") (name "Net-(R202-Pad2)") (class "Default")
      (node (ref "R202") (pin "2") (pinfunction "2_2") (pintype "passive"))
      (node (ref "R203") (pin "1") (pinfunction "1_1") (pintype "passive"))
    )
    (net (code "51") (name "Net-(R209-Pad2)") (class "Default")
      (node (ref "R209") (pin "2") (pinfunction "2_2") (pintype "passive"))
      (node (ref "R210") (pin "1") (pinfunction "1_1") (pintype "passive"))
    )
    (net (code "52") (name "Net-(R212-Pad2)") (class "Default")
      (node (ref "R212") (pin "2") (pinfunction "2_2") (pintype "passive"))
      (node (ref "R213") (pin "1") (pinfunction "1_1") (pintype "passive"))
    )
    (net (code "53") (name "Vvar1") (class "Default")
      (node (ref "C109") (pin "1") (pinfunction "1_1") (pintype "passive"))
      (node (ref "IC39") (pin "1") (pinfunction "S2_1") (pintype "passive"))
      (node (ref "IC39") (pin "5") (pinfunction "D1_5") (pintype "passive"))
      (node (ref "IC39") (pin "6") (pinfunction "D1_6") (pintype "passive"))
      (node (ref "IC41") (pin "7") (pinfunction "VCCB_7") (pintype "passive"))
    )
    (net (code "54") (name "Vvar2") (class "Default")
      (node (ref "C101") (pin "1") (pinfunction "1_1") (pintype "passive"))
      (node (ref "IC27") (pin "1") (pinfunction "S2_1") (pintype "passive"))
      (node (ref "IC27") (pin "5") (pinfunction "D1_5") (pintype "passive"))
      (node (ref "IC27") (pin "6") (pinfunction "D1_6") (pintype "passive"))
      (node (ref "IC29") (pin "7") (pinfunction "VCCB_7") (pintype "passive"))
    )
    (net (code "55") (name "Vvar3") (class "Default")
      (node (ref "C107") (pin "1") (pinfunction "1_1") (pintype "passive"))
      (node (ref "IC33") (pin "1") (pinfunction "S2_1") (pintype "passive"))
      (node (ref "IC33") (pin "5") (pinfunction "D1_5") (pintype "passive"))
      (node (ref "IC33") (pin "6") (pinfunction "D1_6") (pintype "passive"))
      (node (ref "IC36") (pin "7") (pinfunction "VCCB_7") (pintype "passive"))
    )
    (net (code "56") (name "Vvar4") (class "Default")
      (node (ref "C111") (pin "1") (pinfunction "1_1") (pintype "passive"))
      (node (ref "IC40") (pin "1") (pinfunction "S2_1") (pintype "passive"))
      (node (ref "IC40") (pin "5") (pinfunction "D1_5") (pintype "passive"))
      (node (ref "IC40") (pin "6") (pinfunction "D1_6") (pintype "passive"))
      (node (ref "IC42") (pin "7") (pinfunction "VCCB_7") (pintype "passive"))
    )
    (net (code "57") (name "Vvar5") (class "Default")
      (node (ref "C105") (pin "1") (pinfunction "1_1") (pintype "passive"))
      (node (ref "IC34") (pin "1") (pinfunction "S2_1") (pintype "passive"))
      (node (ref "IC34") (pin "5") (pinfunction "D1_5") (pintype "passive"))
      (node (ref "IC34") (pin "6") (pinfunction "D1_6") (pintype "passive"))
      (node (ref "IC35") (pin "7") (pinfunction "VCCB_7") (pintype "passive"))
    )
    (net (code "58") (name "Vvar6") (class "Default")
      (node (ref "C103") (pin "1") (pinfunction "1_1") (pintype "passive"))
      (node (ref "IC28") (pin "1") (pinfunction "S2_1") (pintype "passive"))
      (node (ref "IC28") (pin "5") (pinfunction "D1_5") (pintype "passive"))
      (node (ref "IC28") (pin "6") (pinfunction "D1_6") (pintype "passive"))
      (node (ref "IC30") (pin "7") (pinfunction "VCCB_7") (pintype "passive"))
    )
  )
)
